# CWs_RFLink_Schematic.net
KiCad netlist of a schematic drawn in Altium Designer
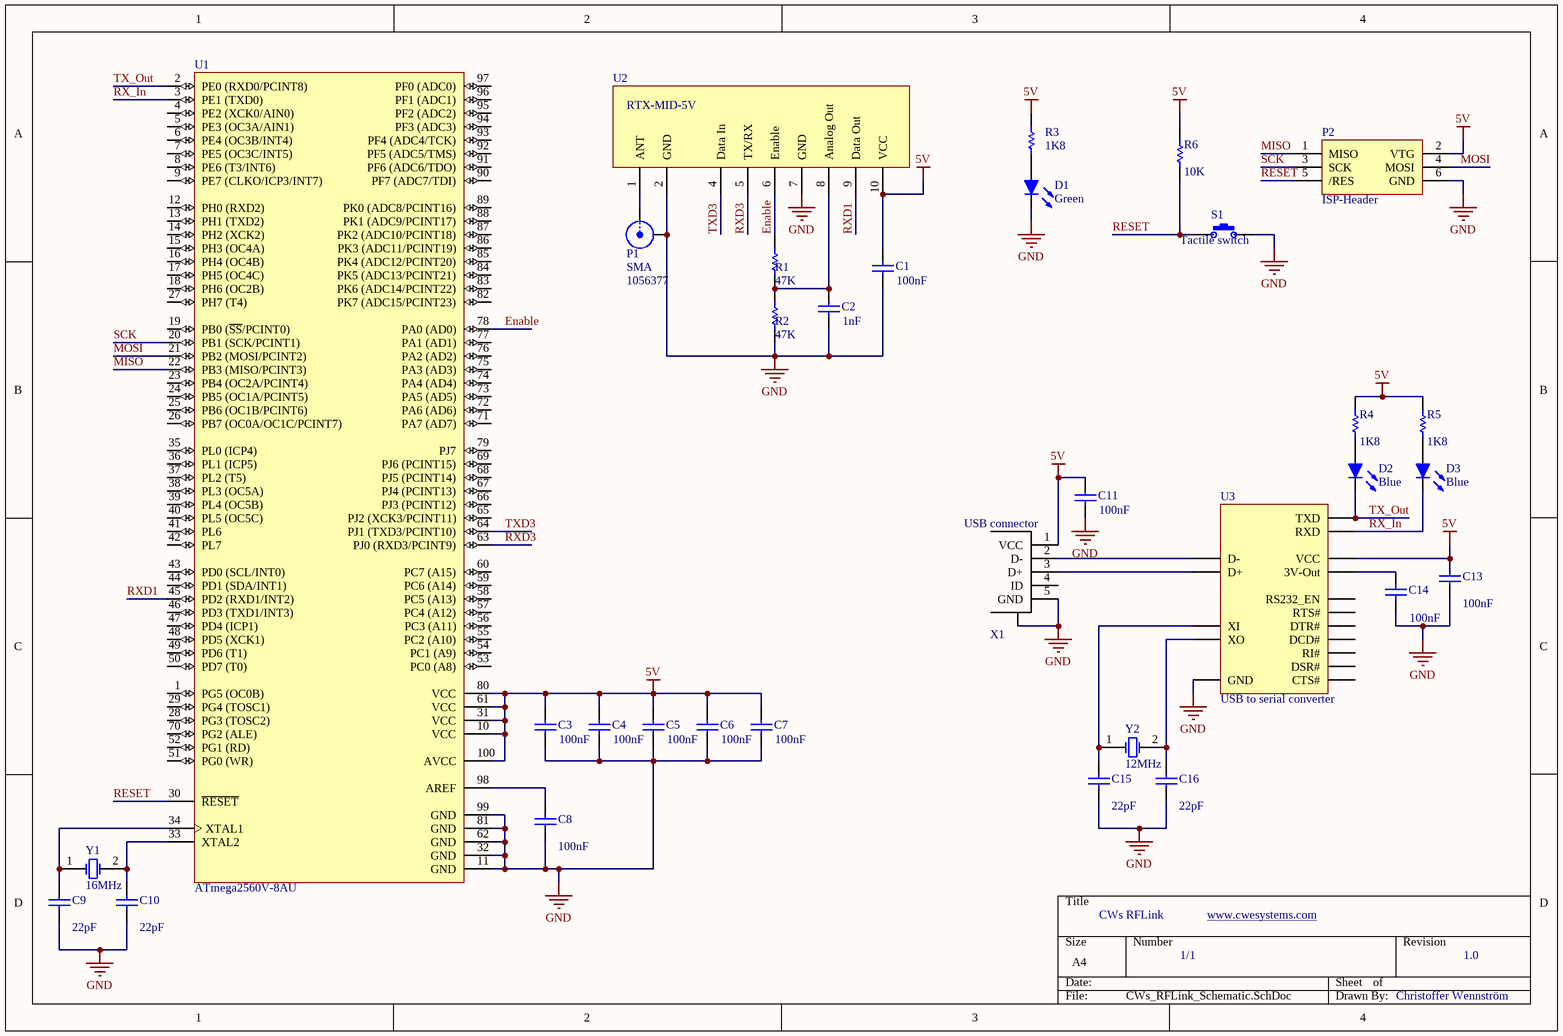
[diagram p0: CWs_RFLink_Schematic.SchDoc]

(export (version "E")
  (design (tool "Eeschema 10.0.6"))
  (components
    (comp (ref "C1")
      (value "100nF")
      (footprint "C-0805")
      (description "Capacitor")
      (fields (field (name "Comment") "Cap") (field (name "PUBLISHER") "Altium Limited"))
      (libsource (lib "crille") (part "Cap"))
    )
    (comp (ref "C2")
      (value "1nF")
      (footprint "C-0805")
      (description "Capacitor")
      (fields (field (name "Comment") "Cap") (field (name "PUBLISHER") "Altium Limited"))
      (libsource (lib "crille") (part "Cap"))
    )
    (comp (ref "C3")
      (value "100nF")
      (footprint "C-0805")
      (description "Capacitor")
      (fields (field (name "Comment") "Cap") (field (name "PUBLISHER") "Altium Limited"))
      (libsource (lib "crille") (part "Cap"))
    )
    (comp (ref "C4")
      (value "100nF")
      (footprint "C-0805")
      (description "Capacitor")
      (fields (field (name "Comment") "Cap") (field (name "PUBLISHER") "Altium Limited"))
      (libsource (lib "crille") (part "Cap"))
    )
    (comp (ref "C5")
      (value "100nF")
      (footprint "C-0805")
      (description "Capacitor")
      (fields (field (name "Comment") "Cap") (field (name "PUBLISHER") "Altium Limited"))
      (libsource (lib "crille") (part "Cap"))
    )
    (comp (ref "C6")
      (value "100nF")
      (footprint "C-0805")
      (description "Capacitor")
      (fields (field (name "Comment") "Cap") (field (name "PUBLISHER") "Altium Limited"))
      (libsource (lib "crille") (part "Cap"))
    )
    (comp (ref "C7")
      (value "100nF")
      (footprint "C-0805")
      (description "Capacitor")
      (fields (field (name "Comment") "Cap") (field (name "PUBLISHER") "Altium Limited"))
      (libsource (lib "crille") (part "Cap"))
    )
    (comp (ref "C8")
      (value "100nF")
      (footprint "C-0805")
      (description "Capacitor")
      (fields (field (name "Comment") "Cap") (field (name "PUBLISHER") "Altium Limited"))
      (libsource (lib "crille") (part "Cap"))
    )
    (comp (ref "C9")
      (value "22pF")
      (footprint "C-0805")
      (description "Capacitor")
      (fields (field (name "Comment") "Cap") (field (name "PUBLISHER") "Altium Limited"))
      (libsource (lib "crille") (part "Cap"))
    )
    (comp (ref "C10")
      (value "22pF")
      (footprint "C-0805")
      (description "Capacitor")
      (fields (field (name "Comment") "Cap") (field (name "PUBLISHER") "Altium Limited"))
      (libsource (lib "crille") (part "Cap"))
    )
    (comp (ref "C11")
      (value "100nF")
      (footprint "C-0805")
      (description "Capacitor")
      (fields (field (name "Comment") "Cap") (field (name "PUBLISHER") "Altium Limited"))
      (libsource (lib "crille") (part "Cap"))
    )
    (comp (ref "C13")
      (value "100nF")
      (footprint "C-0805")
      (description "Capacitor")
      (fields (field (name "Comment") "Cap") (field (name "PUBLISHER") "Altium Limited"))
      (libsource (lib "crille") (part "Cap"))
    )
    (comp (ref "C14")
      (value "100nF")
      (footprint "C-0805")
      (description "Capacitor")
      (fields (field (name "Comment") "Cap") (field (name "PUBLISHER") "Altium Limited"))
      (libsource (lib "crille") (part "Cap"))
    )
    (comp (ref "C15")
      (value "22pF")
      (footprint "C-0805")
      (description "Capacitor")
      (fields (field (name "Comment") "Cap") (field (name "PUBLISHER") "Altium Limited"))
      (libsource (lib "crille") (part "Cap"))
    )
    (comp (ref "C16")
      (value "22pF")
      (footprint "C-0805")
      (description "Capacitor")
      (fields (field (name "Comment") "Cap") (field (name "PUBLISHER") "Altium Limited"))
      (libsource (lib "crille") (part "Cap"))
    )
    (comp (ref "D1")
      (value "Green")
      (footprint "LED0805")
      (description "LED")
      (fields (field (name "PUBLISHER") "Altium Limited"))
      (libsource (lib "crille") (part "LED"))
    )
    (comp (ref "D2")
      (value "Blue")
      (footprint "LED0805")
      (description "LED")
      (fields (field (name "PUBLISHER") "Altium Limited"))
      (libsource (lib "crille") (part "LED"))
    )
    (comp (ref "D3")
      (value "Blue")
      (footprint "LED0805")
      (description "LED")
      (fields (field (name "PUBLISHER") "Altium Limited"))
      (libsource (lib "crille") (part "LED"))
    )
    (comp (ref "P1")
      (value "SMA")
      (footprint "SMA")
      (description "SMA Rak kontakt")
      (fields (field (name "SUPPLIER PART NUMBER 1") "1056377") (field (name "PUBLISHER") "Altium Limited"))
      (libsource (lib "crille") (part "SMA"))
    )
    (comp (ref "P2")
      (value "ISP-Header")
      (footprint "HDR2X3")
      (description "Header, 3-Pin, Dual row")
      (fields (field (name "PUBLISHER") "Altium Limited"))
      (libsource (lib "crille") (part "ISP-Header"))
    )
    (comp (ref "R1")
      (value "47K")
      (footprint "res-0805")
      (description "Resistor")
      (fields (field (name "Comment") "Res1") (field (name "PUBLISHER") "Altium Limited"))
      (libsource (lib "crille") (part "Res1"))
    )
    (comp (ref "R2")
      (value "47K")
      (footprint "res-0805")
      (description "Resistor")
      (fields (field (name "Comment") "Res1") (field (name "PUBLISHER") "Altium Limited"))
      (libsource (lib "crille") (part "Res1"))
    )
    (comp (ref "R3")
      (value "1K8")
      (footprint "res-0805")
      (description "Resistor")
      (fields (field (name "Comment") "Res1") (field (name "PUBLISHER") "Altium Limited"))
      (libsource (lib "crille") (part "Res1"))
    )
    (comp (ref "R4")
      (value "1K8")
      (footprint "res-0805")
      (description "Resistor")
      (fields (field (name "Comment") "Res1") (field (name "PUBLISHER") "Altium Limited"))
      (libsource (lib "crille") (part "Res1"))
    )
    (comp (ref "R5")
      (value "1K8")
      (footprint "res-0805")
      (description "Resistor")
      (fields (field (name "Comment") "Res1") (field (name "PUBLISHER") "Altium Limited"))
      (libsource (lib "crille") (part "Res1"))
    )
    (comp (ref "R6")
      (value "10K")
      (footprint "res-0805")
      (description "Resistor")
      (fields (field (name "Comment") "Res1") (field (name "PUBLISHER") "Altium Limited"))
      (libsource (lib "crille") (part "Res1"))
    )
    (comp (ref "S1")
      (value "Tactile switch")
      (footprint "B3FS-1010")
      (description "Tactile Switch")
      (libsource (lib "crille") (part "Tactile switch"))
    )
    (comp (ref "U1")
      (value "ATmega2560V-8AU")
      (footprint "100A_N")
      (libsource (lib "crille") (part "ATmega2560V-8AU"))
    )
    (comp (ref "U2")
      (value "RTX-MID-5V")
      (footprint "RTX-MID-5V")
      (description "Aurel RTX-MID-5V")
      (libsource (lib "crille") (part "RTX-MID-5V"))
    )
    (comp (ref "U3")
      (value "USB to serial converter")
      (footprint "SOIC16_M")
      (libsource (lib "crille") (part "CH340G"))
    )
    (comp (ref "X1")
      (value "USB connector")
      (footprint "USBmicro")
      (libsource (lib "crille") (part "USB_connector"))
    )
    (comp (ref "Y1")
      (value "16MHz")
      (footprint "5032 crystal")
      (description "Crystal Oscillator")
      (fields (field (name "PUBLISHER") "Altium Limited"))
      (libsource (lib "crille") (part "Kristall"))
    )
    (comp (ref "Y2")
      (value "12MHz")
      (footprint "5032 crystal")
      (description "Crystal Oscillator")
      (fields (field (name "PUBLISHER") "Altium Limited"))
      (libsource (lib "crille") (part "Kristall"))
    )
  )
  (nets
    (net (code "1") (name "/Enable") (class "Default")
      (node (ref "R1") (pin "2") (pinfunction "2_2") (pintype "passive"))
      (node (ref "U1") (pin "78") (pinfunction "PA0_(AD0)_78") (pintype "bidirectional"))
      (node (ref "U2") (pin "6") (pinfunction "Enable_6") (pintype "passive"))
    )
    (net (code "2") (name "/MISO") (class "Default")
      (node (ref "P2") (pin "1") (pinfunction "MISO_1") (pintype "passive"))
      (node (ref "U1") (pin "22") (pinfunction "PB3_(MISO/PCINT3)_22") (pintype "bidirectional"))
    )
    (net (code "3") (name "/MOSI") (class "Default")
      (node (ref "P2") (pin "4") (pinfunction "MOSI_4") (pintype "passive"))
      (node (ref "U1") (pin "21") (pinfunction "PB2_(MOSI/PCINT2)_21") (pintype "bidirectional"))
    )
    (net (code "4") (name "/RESET") (class "Default")
      (node (ref "P2") (pin "5") (pinfunction "/RES_5") (pintype "passive"))
      (node (ref "R6") (pin "1") (pinfunction "1_1") (pintype "passive"))
      (node (ref "S1") (pin "1") (pinfunction "1_1") (pintype "passive"))
      (node (ref "U1") (pin "30") (pinfunction "~{RESET}_30") (pintype "passive"))
    )
    (net (code "5") (name "/RXD1") (class "Default")
      (node (ref "U1") (pin "45") (pinfunction "PD2_(RXD1/INT2)_45") (pintype "bidirectional"))
      (node (ref "U2") (pin "9") (pinfunction "Data_Out_9") (pintype "passive"))
    )
    (net (code "6") (name "/RXD3") (class "Default")
      (node (ref "U1") (pin "63") (pinfunction "PJ0_(RXD3/PCINT9)_63") (pintype "bidirectional"))
      (node (ref "U2") (pin "5") (pinfunction "TX/RX_5") (pintype "passive"))
    )
    (net (code "7") (name "/RX_In") (class "Default")
      (node (ref "D3") (pin "2") (pinfunction "K_2") (pintype "passive"))
      (node (ref "U1") (pin "3") (pinfunction "PE1_(TXD0)_3") (pintype "bidirectional"))
      (node (ref "U3") (pin "3") (pinfunction "RXD_3") (pintype "passive"))
    )
    (net (code "8") (name "/SCK") (class "Default")
      (node (ref "P2") (pin "3") (pinfunction "SCK_3") (pintype "passive"))
      (node (ref "U1") (pin "20") (pinfunction "PB1_(SCK/PCINT1)_20") (pintype "bidirectional"))
    )
    (net (code "9") (name "/TXD3") (class "Default")
      (node (ref "U1") (pin "64") (pinfunction "PJ1_(TXD3/PCINT10)_64") (pintype "bidirectional"))
      (node (ref "U2") (pin "4") (pinfunction "Data_In_4") (pintype "passive"))
    )
    (net (code "10") (name "/TX_Out") (class "Default")
      (node (ref "D2") (pin "2") (pinfunction "K_2") (pintype "passive"))
      (node (ref "U1") (pin "2") (pinfunction "PE0_(RXD0/PCINT8)_2") (pintype "bidirectional"))
      (node (ref "U3") (pin "2") (pinfunction "TXD_2") (pintype "passive"))
    )
    (net (code "11") (name "5V") (class "Default")
      (node (ref "C1") (pin "2") (pinfunction "2_2") (pintype "passive"))
      (node (ref "C11") (pin "2") (pinfunction "2_2") (pintype "passive"))
      (node (ref "C13") (pin "2") (pinfunction "2_2") (pintype "passive"))
      (node (ref "C3") (pin "2") (pinfunction "2_2") (pintype "passive"))
      (node (ref "C4") (pin "2") (pinfunction "2_2") (pintype "passive"))
      (node (ref "C5") (pin "2") (pinfunction "2_2") (pintype "passive"))
      (node (ref "C6") (pin "2") (pinfunction "2_2") (pintype "passive"))
      (node (ref "C7") (pin "2") (pinfunction "2_2") (pintype "passive"))
      (node (ref "P2") (pin "2") (pinfunction "VTG_2") (pintype "power_in"))
      (node (ref "R3") (pin "1") (pinfunction "1_1") (pintype "passive"))
      (node (ref "R4") (pin "2") (pinfunction "2_2") (pintype "passive"))
      (node (ref "R5") (pin "2") (pinfunction "2_2") (pintype "passive"))
      (node (ref "R6") (pin "2") (pinfunction "2_2") (pintype "passive"))
      (node (ref "U1") (pin "10") (pinfunction "VCC_10") (pintype "power_in"))
      (node (ref "U1") (pin "100") (pinfunction "AVCC_100") (pintype "power_in"))
      (node (ref "U1") (pin "31") (pinfunction "VCC_31") (pintype "power_in"))
      (node (ref "U1") (pin "61") (pinfunction "VCC_61") (pintype "power_in"))
      (node (ref "U1") (pin "80") (pinfunction "VCC_80") (pintype "power_in"))
      (node (ref "U2") (pin "10") (pinfunction "VCC_10") (pintype "passive"))
      (node (ref "U3") (pin "16") (pinfunction "VCC_16") (pintype "power_in"))
      (node (ref "X1") (pin "1") (pinfunction "VCC_1") (pintype "passive"))
    )
    (net (code "12") (name "GND") (class "Default")
      (node (ref "C1") (pin "1") (pinfunction "1_1") (pintype "passive"))
      (node (ref "C10") (pin "1") (pinfunction "1_1") (pintype "passive"))
      (node (ref "C11") (pin "1") (pinfunction "1_1") (pintype "passive"))
      (node (ref "C13") (pin "1") (pinfunction "1_1") (pintype "passive"))
      (node (ref "C14") (pin "1") (pinfunction "1_1") (pintype "passive"))
      (node (ref "C15") (pin "1") (pinfunction "1_1") (pintype "passive"))
      (node (ref "C16") (pin "1") (pinfunction "1_1") (pintype "passive"))
      (node (ref "C2") (pin "1") (pinfunction "1_1") (pintype "passive"))
      (node (ref "C3") (pin "1") (pinfunction "1_1") (pintype "passive"))
      (node (ref "C4") (pin "1") (pinfunction "1_1") (pintype "passive"))
      (node (ref "C5") (pin "1") (pinfunction "1_1") (pintype "passive"))
      (node (ref "C6") (pin "1") (pinfunction "1_1") (pintype "passive"))
      (node (ref "C7") (pin "1") (pinfunction "1_1") (pintype "passive"))
      (node (ref "C8") (pin "1") (pinfunction "1_1") (pintype "passive"))
      (node (ref "C9") (pin "1") (pinfunction "1_1") (pintype "passive"))
      (node (ref "D1") (pin "2") (pinfunction "K_2") (pintype "passive"))
      (node (ref "P1") (pin "2") (pinfunction "Y_2") (pintype "passive"))
      (node (ref "P2") (pin "6") (pinfunction "GND_6") (pintype "power_in"))
      (node (ref "R2") (pin "1") (pinfunction "1_1") (pintype "passive"))
      (node (ref "S1") (pin "2") (pinfunction "2_2") (pintype "passive"))
      (node (ref "U1") (pin "11") (pinfunction "GND_11") (pintype "power_in"))
      (node (ref "U1") (pin "32") (pinfunction "GND_32") (pintype "power_in"))
      (node (ref "U1") (pin "62") (pinfunction "GND_62") (pintype "power_in"))
      (node (ref "U1") (pin "81") (pinfunction "GND_81") (pintype "power_in"))
      (node (ref "U1") (pin "99") (pinfunction "GND_99") (pintype "power_in"))
      (node (ref "U2") (pin "2") (pinfunction "GND_2") (pintype "passive"))
      (node (ref "U2") (pin "7") (pinfunction "GND_7") (pintype "passive"))
      (node (ref "U3") (pin "1") (pinfunction "GND_1") (pintype "power_in"))
      (node (ref "X1") (pin "5") (pinfunction "GND_5") (pintype "passive"))
    )
    (net (code "13") (name "Net-(D1-A)") (class "Default")
      (node (ref "D1") (pin "1") (pinfunction "A_1") (pintype "passive"))
      (node (ref "R3") (pin "2") (pinfunction "2_2") (pintype "passive"))
    )
    (net (code "14") (name "Net-(D2-A)") (class "Default")
      (node (ref "D2") (pin "1") (pinfunction "A_1") (pintype "passive"))
      (node (ref "R4") (pin "1") (pinfunction "1_1") (pintype "passive"))
    )
    (net (code "15") (name "Net-(D3-A)") (class "Default")
      (node (ref "D3") (pin "1") (pinfunction "A_1") (pintype "passive"))
      (node (ref "R5") (pin "1") (pinfunction "1_1") (pintype "passive"))
    )
    (net (code "16") (name "Net-(P1-X)") (class "Default")
      (node (ref "P1") (pin "1") (pinfunction "X_1") (pintype "passive"))
      (node (ref "U2") (pin "1") (pinfunction "ANT_1") (pintype "passive"))
    )
    (net (code "17") (name "Net-(U1-AREF)") (class "Default")
      (node (ref "C8") (pin "2") (pinfunction "2_2") (pintype "passive"))
      (node (ref "U1") (pin "98") (pinfunction "AREF_98") (pintype "power_in"))
    )
    (net (code "18") (name "Net-(U1-XTAL1)") (class "Default")
      (node (ref "C9") (pin "2") (pinfunction "2_2") (pintype "passive"))
      (node (ref "U1") (pin "34") (pinfunction "XTAL1_34") (pintype "passive"))
      (node (ref "Y1") (pin "1") (pinfunction "OSC1_1") (pintype "passive"))
    )
    (net (code "19") (name "Net-(U1-XTAL2)") (class "Default")
      (node (ref "C10") (pin "2") (pinfunction "2_2") (pintype "passive"))
      (node (ref "U1") (pin "33") (pinfunction "XTAL2_33") (pintype "passive"))
      (node (ref "Y1") (pin "2") (pinfunction "OSC2_2") (pintype "passive"))
    )
    (net (code "20") (name "Net-(U2-Analog_Out)") (class "Default")
      (node (ref "C2") (pin "2") (pinfunction "2_2") (pintype "passive"))
      (node (ref "R1") (pin "1") (pinfunction "1_1") (pintype "passive"))
      (node (ref "R2") (pin "2") (pinfunction "2_2") (pintype "passive"))
      (node (ref "U2") (pin "8") (pinfunction "Analog_Out_8") (pintype "passive"))
    )
    (net (code "21") (name "Net-(U3-3V-Out)") (class "Default")
      (node (ref "C14") (pin "2") (pinfunction "2_2") (pintype "passive"))
      (node (ref "U3") (pin "4") (pinfunction "3V-Out_4") (pintype "power_in"))
    )
    (net (code "22") (name "Net-(U3-D+)") (class "Default")
      (node (ref "U3") (pin "5") (pinfunction "D+_5") (pintype "passive"))
      (node (ref "X1") (pin "3") (pinfunction "D+_3") (pintype "passive"))
    )
    (net (code "23") (name "Net-(U3-D-)") (class "Default")
      (node (ref "U3") (pin "6") (pinfunction "D-_6") (pintype "passive"))
      (node (ref "X1") (pin "2") (pinfunction "D-_2") (pintype "passive"))
    )
    (net (code "24") (name "Net-(U3-XI)") (class "Default")
      (node (ref "C15") (pin "2") (pinfunction "2_2") (pintype "passive"))
      (node (ref "U3") (pin "7") (pinfunction "XI_7") (pintype "passive"))
      (node (ref "Y2") (pin "1") (pinfunction "OSC1_1") (pintype "passive"))
    )
    (net (code "25") (name "Net-(U3-XO)") (class "Default")
      (node (ref "C16") (pin "2") (pinfunction "2_2") (pintype "passive"))
      (node (ref "U3") (pin "8") (pinfunction "XO_8") (pintype "passive"))
      (node (ref "Y2") (pin "2") (pinfunction "OSC2_2") (pintype "passive"))
    )
    (net (code "26") (name "unconnected-(U1-PA1_(AD1)-Pad77)") (class "Default")
      (node (ref "U1") (pin "77") (pinfunction "PA1_(AD1)_77") (pintype "bidirectional"))
    )
    (net (code "27") (name "unconnected-(U1-PA2_(AD2)-Pad76)") (class "Default")
      (node (ref "U1") (pin "76") (pinfunction "PA2_(AD2)_76") (pintype "bidirectional"))
    )
    (net (code "28") (name "unconnected-(U1-PA3_(AD3)-Pad75)") (class "Default")
      (node (ref "U1") (pin "75") (pinfunction "PA3_(AD3)_75") (pintype "bidirectional"))
    )
    (net (code "29") (name "unconnected-(U1-PA4_(AD4)-Pad74)") (class "Default")
      (node (ref "U1") (pin "74") (pinfunction "PA4_(AD4)_74") (pintype "bidirectional"))
    )
    (net (code "30") (name "unconnected-(U1-PA5_(AD5)-Pad73)") (class "Default")
      (node (ref "U1") (pin "73") (pinfunction "PA5_(AD5)_73") (pintype "bidirectional"))
    )
    (net (code "31") (name "unconnected-(U1-PA6_(AD6)-Pad72)") (class "Default")
      (node (ref "U1") (pin "72") (pinfunction "PA6_(AD6)_72") (pintype "bidirectional"))
    )
    (net (code "32") (name "unconnected-(U1-PA7_(AD7)-Pad71)") (class "Default")
      (node (ref "U1") (pin "71") (pinfunction "PA7_(AD7)_71") (pintype "bidirectional"))
    )
    (net (code "33") (name "unconnected-(U1-PB0_(~{SS}{slash}PCINT0)-Pad19)") (class "Default")
      (node (ref "U1") (pin "19") (pinfunction "PB0_(~{SS}/PCINT0)_19") (pintype "bidirectional"))
    )
    (net (code "34") (name "unconnected-(U1-PB4_(OC2A{slash}PCINT4)-Pad23)") (class "Default")
      (node (ref "U1") (pin "23") (pinfunction "PB4_(OC2A/PCINT4)_23") (pintype "bidirectional"))
    )
    (net (code "35") (name "unconnected-(U1-PB5_(OC1A{slash}PCINT5)-Pad24)") (class "Default")
      (node (ref "U1") (pin "24") (pinfunction "PB5_(OC1A/PCINT5)_24") (pintype "bidirectional"))
    )
    (net (code "36") (name "unconnected-(U1-PB6_(OC1B{slash}PCINT6)-Pad25)") (class "Default")
      (node (ref "U1") (pin "25") (pinfunction "PB6_(OC1B/PCINT6)_25") (pintype "bidirectional"))
    )
    (net (code "37") (name "unconnected-(U1-PB7_(OC0A{slash}OC1C{slash}PCINT7)-Pad26)") (class "Default")
      (node (ref "U1") (pin "26") (pinfunction "PB7_(OC0A/OC1C/PCINT7)_26") (pintype "bidirectional"))
    )
    (net (code "38") (name "unconnected-(U1-PC0_(A8)-Pad53)") (class "Default")
      (node (ref "U1") (pin "53") (pinfunction "PC0_(A8)_53") (pintype "bidirectional"))
    )
    (net (code "39") (name "unconnected-(U1-PC1_(A9)-Pad54)") (class "Default")
      (node (ref "U1") (pin "54") (pinfunction "PC1_(A9)_54") (pintype "bidirectional"))
    )
    (net (code "40") (name "unconnected-(U1-PC2_(A10)-Pad55)") (class "Default")
      (node (ref "U1") (pin "55") (pinfunction "PC2_(A10)_55") (pintype "bidirectional"))
    )
    (net (code "41") (name "unconnected-(U1-PC3_(A11)-Pad56)") (class "Default")
      (node (ref "U1") (pin "56") (pinfunction "PC3_(A11)_56") (pintype "bidirectional"))
    )
    (net (code "42") (name "unconnected-(U1-PC4_(A12)-Pad57)") (class "Default")
      (node (ref "U1") (pin "57") (pinfunction "PC4_(A12)_57") (pintype "bidirectional"))
    )
    (net (code "43") (name "unconnected-(U1-PC5_(A13)-Pad58)") (class "Default")
      (node (ref "U1") (pin "58") (pinfunction "PC5_(A13)_58") (pintype "bidirectional"))
    )
    (net (code "44") (name "unconnected-(U1-PC6_(A14)-Pad59)") (class "Default")
      (node (ref "U1") (pin "59") (pinfunction "PC6_(A14)_59") (pintype "bidirectional"))
    )
    (net (code "45") (name "unconnected-(U1-PC7_(A15)-Pad60)") (class "Default")
      (node (ref "U1") (pin "60") (pinfunction "PC7_(A15)_60") (pintype "bidirectional"))
    )
    (net (code "46") (name "unconnected-(U1-PD0_(SCL{slash}INT0)-Pad43)") (class "Default")
      (node (ref "U1") (pin "43") (pinfunction "PD0_(SCL/INT0)_43") (pintype "bidirectional"))
    )
    (net (code "47") (name "unconnected-(U1-PD1_(SDA{slash}INT1)-Pad44)") (class "Default")
      (node (ref "U1") (pin "44") (pinfunction "PD1_(SDA/INT1)_44") (pintype "bidirectional"))
    )
    (net (code "48") (name "unconnected-(U1-PD3_(TXD1{slash}INT3)-Pad46)") (class "Default")
      (node (ref "U1") (pin "46") (pinfunction "PD3_(TXD1/INT3)_46") (pintype "bidirectional"))
    )
    (net (code "49") (name "unconnected-(U1-PD4_(ICP1)-Pad47)") (class "Default")
      (node (ref "U1") (pin "47") (pinfunction "PD4_(ICP1)_47") (pintype "bidirectional"))
    )
    (net (code "50") (name "unconnected-(U1-PD5_(XCK1)-Pad48)") (class "Default")
      (node (ref "U1") (pin "48") (pinfunction "PD5_(XCK1)_48") (pintype "bidirectional"))
    )
    (net (code "51") (name "unconnected-(U1-PD6_(T1)-Pad49)") (class "Default")
      (node (ref "U1") (pin "49") (pinfunction "PD6_(T1)_49") (pintype "bidirectional"))
    )
    (net (code "52") (name "unconnected-(U1-PD7_(T0)-Pad50)") (class "Default")
      (node (ref "U1") (pin "50") (pinfunction "PD7_(T0)_50") (pintype "bidirectional"))
    )
    (net (code "53") (name "unconnected-(U1-PE2_(XCK0{slash}AIN0)-Pad4)") (class "Default")
      (node (ref "U1") (pin "4") (pinfunction "PE2_(XCK0/AIN0)_4") (pintype "bidirectional"))
    )
    (net (code "54") (name "unconnected-(U1-PE3_(OC3A{slash}AIN1)-Pad5)") (class "Default")
      (node (ref "U1") (pin "5") (pinfunction "PE3_(OC3A/AIN1)_5") (pintype "bidirectional"))
    )
    (net (code "55") (name "unconnected-(U1-PE4_(OC3B{slash}INT4)-Pad6)") (class "Default")
      (node (ref "U1") (pin "6") (pinfunction "PE4_(OC3B/INT4)_6") (pintype "bidirectional"))
    )
    (net (code "56") (name "unconnected-(U1-PE5_(OC3C{slash}INT5)-Pad7)") (class "Default")
      (node (ref "U1") (pin "7") (pinfunction "PE5_(OC3C/INT5)_7") (pintype "bidirectional"))
    )
    (net (code "57") (name "unconnected-(U1-PE6_(T3{slash}INT6)-Pad8)") (class "Default")
      (node (ref "U1") (pin "8") (pinfunction "PE6_(T3/INT6)_8") (pintype "bidirectional"))
    )
    (net (code "58") (name "unconnected-(U1-PE7_(CLKO{slash}ICP3{slash}INT7)-Pad9)") (class "Default")
      (node (ref "U1") (pin "9") (pinfunction "PE7_(CLKO/ICP3/INT7)_9") (pintype "bidirectional"))
    )
    (net (code "59") (name "unconnected-(U1-PF0_(ADC0)-Pad97)") (class "Default")
      (node (ref "U1") (pin "97") (pinfunction "PF0_(ADC0)_97") (pintype "bidirectional"))
    )
    (net (code "60") (name "unconnected-(U1-PF1_(ADC1)-Pad96)") (class "Default")
      (node (ref "U1") (pin "96") (pinfunction "PF1_(ADC1)_96") (pintype "bidirectional"))
    )
    (net (code "61") (name "unconnected-(U1-PF2_(ADC2)-Pad95)") (class "Default")
      (node (ref "U1") (pin "95") (pinfunction "PF2_(ADC2)_95") (pintype "bidirectional"))
    )
    (net (code "62") (name "unconnected-(U1-PF3_(ADC3)-Pad94)") (class "Default")
      (node (ref "U1") (pin "94") (pinfunction "PF3_(ADC3)_94") (pintype "bidirectional"))
    )
    (net (code "63") (name "unconnected-(U1-PF4_(ADC4{slash}TCK)-Pad93)") (class "Default")
      (node (ref "U1") (pin "93") (pinfunction "PF4_(ADC4/TCK)_93") (pintype "bidirectional"))
    )
    (net (code "64") (name "unconnected-(U1-PF5_(ADC5{slash}TMS)-Pad92)") (class "Default")
      (node (ref "U1") (pin "92") (pinfunction "PF5_(ADC5/TMS)_92") (pintype "bidirectional"))
    )
    (net (code "65") (name "unconnected-(U1-PF6_(ADC6{slash}TDO)-Pad91)") (class "Default")
      (node (ref "U1") (pin "91") (pinfunction "PF6_(ADC6/TDO)_91") (pintype "bidirectional"))
    )
    (net (code "66") (name "unconnected-(U1-PF7_(ADC7{slash}TDI)-Pad90)") (class "Default")
      (node (ref "U1") (pin "90") (pinfunction "PF7_(ADC7/TDI)_90") (pintype "bidirectional"))
    )
    (net (code "67") (name "unconnected-(U1-PG0_(WR)-Pad51)") (class "Default")
      (node (ref "U1") (pin "51") (pinfunction "PG0_(WR)_51") (pintype "bidirectional"))
    )
    (net (code "68") (name "unconnected-(U1-PG1_(RD)-Pad52)") (class "Default")
      (node (ref "U1") (pin "52") (pinfunction "PG1_(RD)_52") (pintype "bidirectional"))
    )
    (net (code "69") (name "unconnected-(U1-PG2_(ALE)-Pad70)") (class "Default")
      (node (ref "U1") (pin "70") (pinfunction "PG2_(ALE)_70") (pintype "bidirectional"))
    )
    (net (code "70") (name "unconnected-(U1-PG3_(TOSC2)-Pad28)") (class "Default")
      (node (ref "U1") (pin "28") (pinfunction "PG3_(TOSC2)_28") (pintype "bidirectional"))
    )
    (net (code "71") (name "unconnected-(U1-PG4_(TOSC1)-Pad29)") (class "Default")
      (node (ref "U1") (pin "29") (pinfunction "PG4_(TOSC1)_29") (pintype "bidirectional"))
    )
    (net (code "72") (name "unconnected-(U1-PG5_(OC0B)-Pad1)") (class "Default")
      (node (ref "U1") (pin "1") (pinfunction "PG5_(OC0B)_1") (pintype "bidirectional"))
    )
    (net (code "73") (name "unconnected-(U1-PH0_(RXD2)-Pad12)") (class "Default")
      (node (ref "U1") (pin "12") (pinfunction "PH0_(RXD2)_12") (pintype "bidirectional"))
    )
    (net (code "74") (name "unconnected-(U1-PH1_(TXD2)-Pad13)") (class "Default")
      (node (ref "U1") (pin "13") (pinfunction "PH1_(TXD2)_13") (pintype "bidirectional"))
    )
    (net (code "75") (name "unconnected-(U1-PH2_(XCK2)-Pad14)") (class "Default")
      (node (ref "U1") (pin "14") (pinfunction "PH2_(XCK2)_14") (pintype "bidirectional"))
    )
    (net (code "76") (name "unconnected-(U1-PH3_(OC4A)-Pad15)") (class "Default")
      (node (ref "U1") (pin "15") (pinfunction "PH3_(OC4A)_15") (pintype "bidirectional"))
    )
    (net (code "77") (name "unconnected-(U1-PH4_(OC4B)-Pad16)") (class "Default")
      (node (ref "U1") (pin "16") (pinfunction "PH4_(OC4B)_16") (pintype "bidirectional"))
    )
    (net (code "78") (name "unconnected-(U1-PH5_(OC4C)-Pad17)") (class "Default")
      (node (ref "U1") (pin "17") (pinfunction "PH5_(OC4C)_17") (pintype "bidirectional"))
    )
    (net (code "79") (name "unconnected-(U1-PH6_(OC2B)-Pad18)") (class "Default")
      (node (ref "U1") (pin "18") (pinfunction "PH6_(OC2B)_18") (pintype "bidirectional"))
    )
    (net (code "80") (name "unconnected-(U1-PH7_(T4)-Pad27)") (class "Default")
      (node (ref "U1") (pin "27") (pinfunction "PH7_(T4)_27") (pintype "bidirectional"))
    )
    (net (code "81") (name "unconnected-(U1-PJ2_(XCK3{slash}PCINT11)-Pad65)") (class "Default")
      (node (ref "U1") (pin "65") (pinfunction "PJ2_(XCK3/PCINT11)_65") (pintype "bidirectional"))
    )
    (net (code "82") (name "unconnected-(U1-PJ3_(PCINT12)-Pad66)") (class "Default")
      (node (ref "U1") (pin "66") (pinfunction "PJ3_(PCINT12)_66") (pintype "bidirectional"))
    )
    (net (code "83") (name "unconnected-(U1-PJ4_(PCINT13)-Pad67)") (class "Default")
      (node (ref "U1") (pin "67") (pinfunction "PJ4_(PCINT13)_67") (pintype "bidirectional"))
    )
    (net (code "84") (name "unconnected-(U1-PJ5_(PCINT14)-Pad68)") (class "Default")
      (node (ref "U1") (pin "68") (pinfunction "PJ5_(PCINT14)_68") (pintype "bidirectional"))
    )
    (net (code "85") (name "unconnected-(U1-PJ6_(PCINT15)-Pad69)") (class "Default")
      (node (ref "U1") (pin "69") (pinfunction "PJ6_(PCINT15)_69") (pintype "bidirectional"))
    )
    (net (code "86") (name "unconnected-(U1-PJ7-Pad79)") (class "Default")
      (node (ref "U1") (pin "79") (pinfunction "PJ7_79") (pintype "bidirectional"))
    )
    (net (code "87") (name "unconnected-(U1-PK0_(ADC8{slash}PCINT16)-Pad89)") (class "Default")
      (node (ref "U1") (pin "89") (pinfunction "PK0_(ADC8/PCINT16)_89") (pintype "bidirectional"))
    )
    (net (code "88") (name "unconnected-(U1-PK1_(ADC9{slash}PCINT17)-Pad88)") (class "Default")
      (node (ref "U1") (pin "88") (pinfunction "PK1_(ADC9/PCINT17)_88") (pintype "bidirectional"))
    )
    (net (code "89") (name "unconnected-(U1-PK2_(ADC10{slash}PCINT18)-Pad87)") (class "Default")
      (node (ref "U1") (pin "87") (pinfunction "PK2_(ADC10/PCINT18)_87") (pintype "bidirectional"))
    )
    (net (code "90") (name "unconnected-(U1-PK3_(ADC11{slash}PCINT19)-Pad86)") (class "Default")
      (node (ref "U1") (pin "86") (pinfunction "PK3_(ADC11/PCINT19)_86") (pintype "bidirectional"))
    )
    (net (code "91") (name "unconnected-(U1-PK4_(ADC12{slash}PCINT20)-Pad85)") (class "Default")
      (node (ref "U1") (pin "85") (pinfunction "PK4_(ADC12/PCINT20)_85") (pintype "bidirectional"))
    )
    (net (code "92") (name "unconnected-(U1-PK5_(ADC13{slash}PCINT21)-Pad84)") (class "Default")
      (node (ref "U1") (pin "84") (pinfunction "PK5_(ADC13/PCINT21)_84") (pintype "bidirectional"))
    )
    (net (code "93") (name "unconnected-(U1-PK6_(ADC14{slash}PCINT22)-Pad83)") (class "Default")
      (node (ref "U1") (pin "83") (pinfunction "PK6_(ADC14/PCINT22)_83") (pintype "bidirectional"))
    )
    (net (code "94") (name "unconnected-(U1-PK7_(ADC15{slash}PCINT23)-Pad82)") (class "Default")
      (node (ref "U1") (pin "82") (pinfunction "PK7_(ADC15/PCINT23)_82") (pintype "bidirectional"))
    )
    (net (code "95") (name "unconnected-(U1-PL0_(ICP4)-Pad35)") (class "Default")
      (node (ref "U1") (pin "35") (pinfunction "PL0_(ICP4)_35") (pintype "bidirectional"))
    )
    (net (code "96") (name "unconnected-(U1-PL1_(ICP5)-Pad36)") (class "Default")
      (node (ref "U1") (pin "36") (pinfunction "PL1_(ICP5)_36") (pintype "bidirectional"))
    )
    (net (code "97") (name "unconnected-(U1-PL2_(T5)-Pad37)") (class "Default")
      (node (ref "U1") (pin "37") (pinfunction "PL2_(T5)_37") (pintype "bidirectional"))
    )
    (net (code "98") (name "unconnected-(U1-PL3_(OC5A)-Pad38)") (class "Default")
      (node (ref "U1") (pin "38") (pinfunction "PL3_(OC5A)_38") (pintype "bidirectional"))
    )
    (net (code "99") (name "unconnected-(U1-PL4_(OC5B)-Pad39)") (class "Default")
      (node (ref "U1") (pin "39") (pinfunction "PL4_(OC5B)_39") (pintype "bidirectional"))
    )
    (net (code "100") (name "unconnected-(U1-PL5_(OC5C)-Pad40)") (class "Default")
      (node (ref "U1") (pin "40") (pinfunction "PL5_(OC5C)_40") (pintype "bidirectional"))
    )
    (net (code "101") (name "unconnected-(U1-PL6-Pad41)") (class "Default")
      (node (ref "U1") (pin "41") (pinfunction "PL6_41") (pintype "bidirectional"))
    )
    (net (code "102") (name "unconnected-(U1-PL7-Pad42)") (class "Default")
      (node (ref "U1") (pin "42") (pinfunction "PL7_42") (pintype "bidirectional"))
    )
    (net (code "103") (name "unconnected-(U3-CTS#-Pad9)") (class "Default")
      (node (ref "U3") (pin "9") (pinfunction "CTS#_9") (pintype "passive"))
    )
    (net (code "104") (name "unconnected-(U3-DCD#-Pad12)") (class "Default")
      (node (ref "U3") (pin "12") (pinfunction "DCD#_12") (pintype "passive"))
    )
    (net (code "105") (name "unconnected-(U3-DSR#-Pad10)") (class "Default")
      (node (ref "U3") (pin "10") (pinfunction "DSR#_10") (pintype "passive"))
    )
    (net (code "106") (name "unconnected-(U3-DTR#-Pad13)") (class "Default")
      (node (ref "U3") (pin "13") (pinfunction "DTR#_13") (pintype "passive"))
    )
    (net (code "107") (name "unconnected-(U3-RI#-Pad11)") (class "Default")
      (node (ref "U3") (pin "11") (pinfunction "RI#_11") (pintype "passive"))
    )
    (net (code "108") (name "unconnected-(U3-RS232_EN-Pad15)") (class "Default")
      (node (ref "U3") (pin "15") (pinfunction "RS232_EN_15") (pintype "passive"))
    )
    (net (code "109") (name "unconnected-(U3-RTS#-Pad14)") (class "Default")
      (node (ref "U3") (pin "14") (pinfunction "RTS#_14") (pintype "passive"))
    )
    (net (code "110") (name "unconnected-(X1-ID-Pad4)") (class "Default")
      (node (ref "X1") (pin "4") (pinfunction "ID_4") (pintype "passive"))
    )
    (net (code "111") (name "unconnected-(X1-Shield-Pad6)") (class "Default")
      (node (ref "X1") (pin "6") (pinfunction "Shield_6") (pintype "passive"))
    )
  )
)
